# Transceivers.net
KiCad netlist of a schematic drawn in Altium Designer
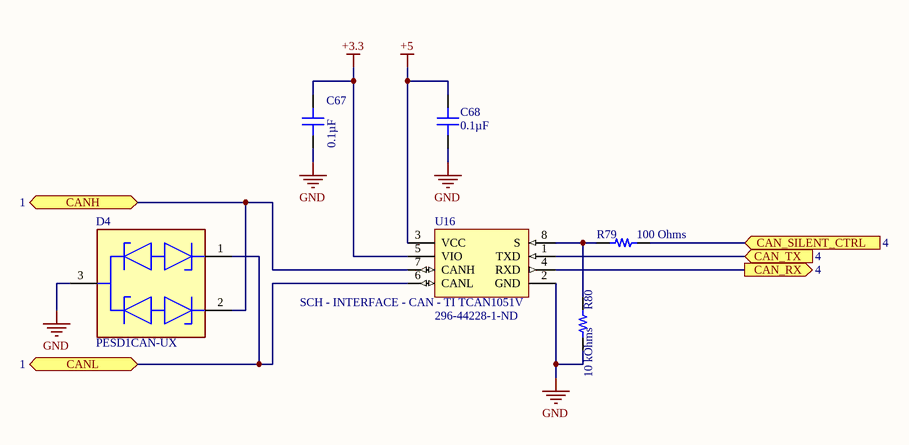
[diagram p0: Transceivers.SchDoc]

(export (version "E")
  (design (tool "Eeschema 10.0.6"))
  (components
    (comp (ref "C67")
      (value "0.1µF")
      (footprint "CAP 0603_1608")
      (description "CAP CER 0.1UF 25V X7R 0603")
      (fields
        (field (name "PART NUMBER") "CL10B104KA8WPNC")
        (field (name "MANUFACTURER") "Samsung Electro-Mechanics")
      )
      (libsource (lib "Celestial Altium Library - altium_library") (part "Capacitor"))
    )
    (comp (ref "C68")
      (value "0.1µF")
      (footprint "CAP 0603_1608")
      (description "CAP CER 0.1UF 25V X7R 0603")
      (fields
        (field (name "PART NUMBER") "CL10B104KA8WPNC")
        (field (name "MANUFACTURER") "Samsung Electro-Mechanics")
      )
      (libsource (lib "Celestial Altium Library - altium_library") (part "Capacitor"))
    )
    (comp (ref "D4")
      (value "PESD1CAN-UX")
      (footprint "FP-SOT323-MFG")
      (description "TVS DIODE 24V 50V SC70-3")
      (libsource (lib "Altium Content Vault") (part "04d57993b6b7b0f5b3c95ba4f97dea0"))
    )
    (comp (ref "R79")
      (value "100 Ohms")
      (footprint "RES 0603_1608")
      (description "RES 100 OHM 1% 1/10W 0603")
      (fields
        (field (name "PART NUMBER") "RMCF0603FG100R")
        (field (name "MANUFACTURER") "Stackpole Electronics Inc")
      )
      (libsource (lib "Celestial Altium Library - altium_library") (part "Resistor"))
    )
    (comp (ref "R80")
      (value "10 kOhms")
      (footprint "RES 0603_1608")
      (description "RES 10K OHM 5% 1/10W 0603")
      (fields
        (field (name "PART NUMBER") "RMCF0603JT10K0")
        (field (name "MANUFACTURER") "Stackpole Electronics Inc")
      )
      (libsource (lib "Celestial Altium Library - altium_library") (part "Resistor"))
    )
    (comp (ref "U16")
      (value "SCH - INTERFACE - CAN - TI TCAN1051V")
      (footprint "PCB - LEADS - SOIC - TI SOIC-8")
      (fields (field (name "SUPPLIER PART NUMBER 1") "296-44228-1-ND"))
      (libsource (lib "HAB_ICs") (part "SCH - INTERFACE - CAN - TI TCAN1051V"))
    )
  )
  (nets
    (net (code "1") (name "+3.3") (class "Default")
      (node (ref "C67") (pin "2") (pinfunction "2_2") (pintype "passive"))
      (node (ref "U16") (pin "5") (pinfunction "VIO_5") (pintype "power_in"))
    )
    (net (code "2") (name "+5") (class "Default")
      (node (ref "C68") (pin "2") (pinfunction "2_2") (pintype "passive"))
      (node (ref "U16") (pin "3") (pinfunction "VCC_3") (pintype "power_in"))
    )
    (net (code "3") (name "/CANH") (class "Default")
      (node (ref "D4") (pin "2") (pinfunction "cathode_2_2") (pintype "passive"))
      (node (ref "U16") (pin "7") (pinfunction "CANH_7") (pintype "bidirectional"))
    )
    (net (code "4") (name "/CANL") (class "Default")
      (node (ref "D4") (pin "1") (pinfunction "cathode_1_1") (pintype "passive"))
      (node (ref "U16") (pin "6") (pinfunction "CANL_6") (pintype "bidirectional"))
    )
    (net (code "5") (name "/CAN_RX") (class "Default")
      (node (ref "U16") (pin "4") (pinfunction "RXD_4") (pintype "output"))
    )
    (net (code "6") (name "/CAN_SILENT_CTRL") (class "Default")
      (node (ref "R79") (pin "2") (pinfunction "2_2") (pintype "passive"))
    )
    (net (code "7") (name "/CAN_TX") (class "Default")
      (node (ref "U16") (pin "1") (pinfunction "TXD_1") (pintype "input"))
    )
    (net (code "8") (name "GND") (class "Default")
      (node (ref "C67") (pin "1") (pinfunction "1_1") (pintype "passive"))
      (node (ref "C68") (pin "1") (pinfunction "1_1") (pintype "passive"))
      (node (ref "D4") (pin "3") (pinfunction "common_cathode_3") (pintype "passive"))
      (node (ref "R80") (pin "1") (pinfunction "1_1") (pintype "passive"))
      (node (ref "U16") (pin "2") (pinfunction "GND_2") (pintype "power_in"))
    )
    (net (code "9") (name "Net-(U16-S)") (class "Default")
      (node (ref "R79") (pin "1") (pinfunction "1_1") (pintype "passive"))
      (node (ref "R80") (pin "2") (pinfunction "2_2") (pintype "passive"))
      (node (ref "U16") (pin "8") (pinfunction "S_8") (pintype "input"))
    )
  )
)
